# Module-PCB.net
KiCad netlist of a schematic drawn in EAGLE
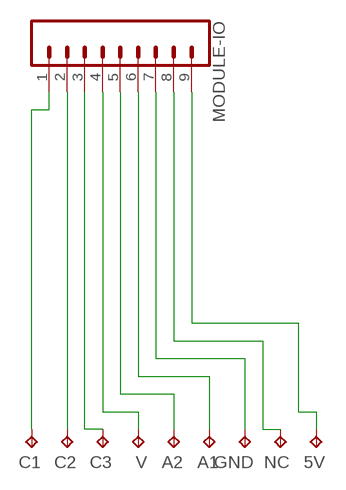
[diagram p0: schematic, sheet 1]

(export (version "E")
  (design (tool "Eeschema 10.0.6"))
  (components
    (comp (ref "5V")
      (value "TPTP20SQ")
      (footprint "eagle-import:TP20SQ")
      (libsource (lib "eagle-import") (part "TPTP20SQ"))
    )
    (comp (ref "A1")
      (value "TPTP20SQ")
      (footprint "eagle-import:TP20SQ")
      (libsource (lib "eagle-import") (part "TPTP20SQ"))
    )
    (comp (ref "A2")
      (value "TPTP20SQ")
      (footprint "eagle-import:TP20SQ")
      (libsource (lib "eagle-import") (part "TPTP20SQ"))
    )
    (comp (ref "C1")
      (value "TPTP20SQ")
      (footprint "eagle-import:TP20SQ")
      (libsource (lib "eagle-import") (part "TPTP20SQ"))
    )
    (comp (ref "C2")
      (value "TPTP20SQ")
      (footprint "eagle-import:TP20SQ")
      (libsource (lib "eagle-import") (part "TPTP20SQ"))
    )
    (comp (ref "C3")
      (value "TPTP20SQ")
      (footprint "eagle-import:TP20SQ")
      (libsource (lib "eagle-import") (part "TPTP20SQ"))
    )
    (comp (ref "GND")
      (value "TPTP20SQ")
      (footprint "eagle-import:TP20SQ")
      (libsource (lib "eagle-import") (part "TPTP20SQ"))
    )
    (comp (ref "MODULE-IO")
      (value "CONN_09")
      (footprint "eagle-import:1X09")
      (libsource (lib "eagle-import") (part "CONN_09"))
    )
    (comp (ref "NC")
      (value "TPTP20SQ")
      (footprint "eagle-import:TP20SQ")
      (libsource (lib "eagle-import") (part "TPTP20SQ"))
    )
    (comp (ref "V")
      (value "TPTP20SQ")
      (footprint "eagle-import:TP20SQ")
      (libsource (lib "eagle-import") (part "TPTP20SQ"))
    )
  )
  (nets
    (net (code "1") (name "Net-(5V-PadTP)") (class "Default")
      (node (ref "5V") (pin "TP") (pinfunction "TP_TP") (pintype "input"))
      (node (ref "MODULE-IO") (pin "9") (pinfunction "9_9") (pintype "passive"))
    )
    (net (code "2") (name "Net-(A1-PadTP)") (class "Default")
      (node (ref "A1") (pin "TP") (pinfunction "TP_TP") (pintype "input"))
      (node (ref "MODULE-IO") (pin "6") (pinfunction "6_6") (pintype "passive"))
    )
    (net (code "3") (name "Net-(A2-PadTP)") (class "Default")
      (node (ref "A2") (pin "TP") (pinfunction "TP_TP") (pintype "input"))
      (node (ref "MODULE-IO") (pin "5") (pinfunction "5_5") (pintype "passive"))
    )
    (net (code "4") (name "Net-(C1-PadTP)") (class "Default")
      (node (ref "C1") (pin "TP") (pinfunction "TP_TP") (pintype "input"))
      (node (ref "MODULE-IO") (pin "1") (pinfunction "1_1") (pintype "passive"))
    )
    (net (code "5") (name "Net-(C2-PadTP)") (class "Default")
      (node (ref "C2") (pin "TP") (pinfunction "TP_TP") (pintype "input"))
      (node (ref "MODULE-IO") (pin "2") (pinfunction "2_2") (pintype "passive"))
    )
    (net (code "6") (name "Net-(C3-PadTP)") (class "Default")
      (node (ref "C3") (pin "TP") (pinfunction "TP_TP") (pintype "input"))
      (node (ref "MODULE-IO") (pin "3") (pinfunction "3_3") (pintype "passive"))
    )
    (net (code "7") (name "Net-(GND-PadTP)") (class "Default")
      (node (ref "GND") (pin "TP") (pinfunction "TP_TP") (pintype "input"))
      (node (ref "MODULE-IO") (pin "7") (pinfunction "7_7") (pintype "passive"))
    )
    (net (code "8") (name "Net-(MODULE-IO-Pad4)") (class "Default")
      (node (ref "MODULE-IO") (pin "4") (pinfunction "4_4") (pintype "passive"))
      (node (ref "V") (pin "TP") (pinfunction "TP_TP") (pintype "input"))
    )
    (net (code "9") (name "Net-(MODULE-IO-Pad8)") (class "Default")
      (node (ref "MODULE-IO") (pin "8") (pinfunction "8_8") (pintype "passive"))
      (node (ref "NC") (pin "TP") (pinfunction "TP_TP") (pintype "input"))
    )
  )
)
